# 3_audioConnectors.net
KiCad netlist of a schematic drawn in Altium Designer
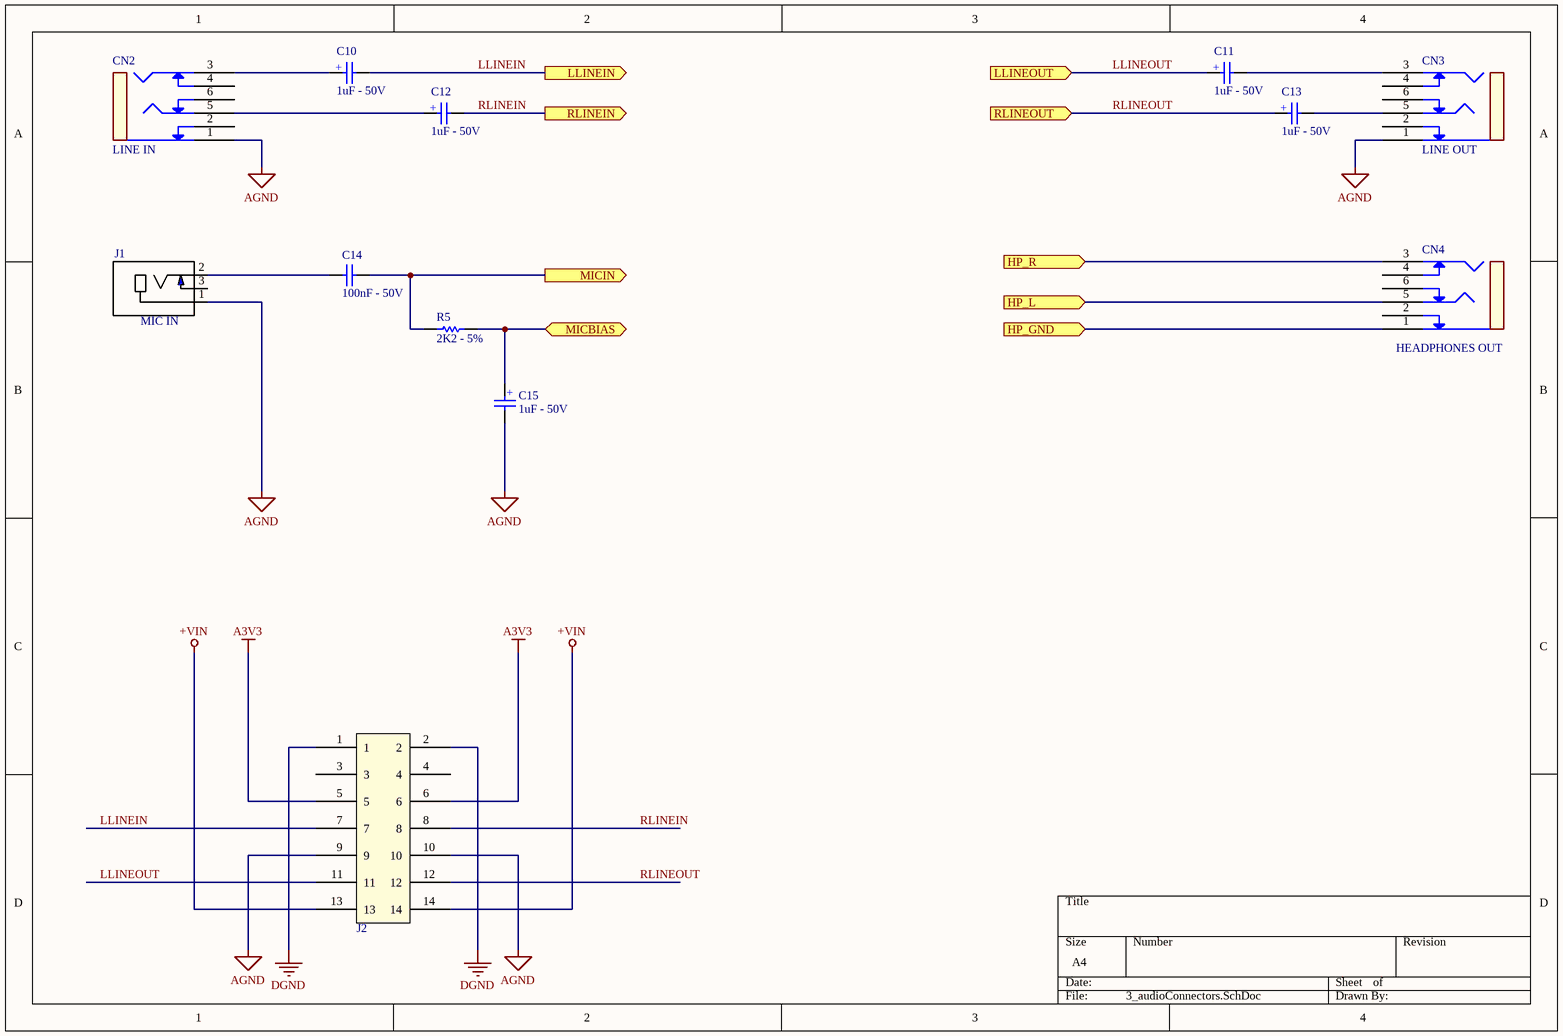
[diagram p0: 3_audioConnectors.SchDoc]

(export (version "E")
  (design (tool "Eeschema 10.0.6"))
  (components
    (comp (ref "C10")
      (value "Capacitor 1 uF - 10%")
      (footprint "CAP/SMD/ELET/5MM/NP")
      (description "Capacitor 1uF, 10%, SMD 0805")
      (fields
        (field (name "MANUFACTURER") "AVX")
        (field (name "PARTNUMBER") "08055C105KAT2A")
        (field (name "VALOR") "1uF - 50V")
      )
      (libsource (lib "Capacitor_smd") (part "1uF - 50V - 10% - 0805 - 3296"))
    )
    (comp (ref "C11")
      (value "Capacitor 1 uF - 10%")
      (footprint "CAP/SMD/ELET/5MM/NP")
      (description "Capacitor 1uF, 10%, SMD 0805")
      (fields
        (field (name "MANUFACTURER") "AVX")
        (field (name "PARTNUMBER") "08055C105KAT2A")
        (field (name "VALOR") "1uF - 50V")
      )
      (libsource (lib "Capacitor_smd") (part "1uF - 50V - 10% - 0805 - 3296"))
    )
    (comp (ref "C12")
      (value "Capacitor 1 uF - 10%")
      (footprint "CAP/SMD/ELET/5MM/NP")
      (description "Capacitor 1uF, 10%, SMD 0805")
      (fields
        (field (name "MANUFACTURER") "AVX")
        (field (name "PARTNUMBER") "08055C105KAT2A")
        (field (name "VALOR") "1uF - 50V")
      )
      (libsource (lib "Capacitor_smd") (part "1uF - 50V - 10% - 0805 - 3296"))
    )
    (comp (ref "C13")
      (value "Capacitor 1 uF - 10%")
      (footprint "CAP/SMD/ELET/5MM/NP")
      (description "Capacitor 1uF, 10%, SMD 0805")
      (fields
        (field (name "MANUFACTURER") "AVX")
        (field (name "PARTNUMBER") "08055C105KAT2A")
        (field (name "VALOR") "1uF - 50V")
      )
      (libsource (lib "Capacitor_smd") (part "1uF - 50V - 10% - 0805 - 3296"))
    )
    (comp (ref "C14")
      (value "Capacitor 100 nF - 10%")
      (footprint "SMD0805-CAP")
      (description "Capacitor 100nF, 10%, SMD 0805")
      (fields
        (field (name "MANUFACTURER") "AVX")
        (field (name "PARTNUMBER") "08055C104KAT2A")
        (field (name "VALOR") "100nF - 50V")
      )
      (libsource (lib "Capacitor_smd") (part "100nF - 50V - 10% - 0805 - 580"))
    )
    (comp (ref "C15")
      (value "Capacitor 1 uF - 10%")
      (footprint "CAP/SMD/ELET/5MM/NP")
      (description "Capacitor 1uF, 10%, SMD 0805")
      (fields
        (field (name "MANUFACTURER") "AVX")
        (field (name "PARTNUMBER") "08055C105KAT2A")
        (field (name "VALOR") "1uF - 50V")
      )
      (libsource (lib "Capacitor_smd") (part "1uF - 50V - 10% - 0805 - 3296"))
    )
    (comp (ref "CN2")
      (value "LINE IN")
      (footprint "CNC/P10/.080")
      (description "Conector JACK P10 ST P/ PC")
      (libsource (lib "") (part "CNC JACK P10 ST P/ PCI, HORIZ, TP - 749_1"))
    )
    (comp (ref "CN3")
      (value "LINE OUT")
      (footprint "CNC/P10/.080")
      (description "Conector JACK P10 ST P/ PC")
      (libsource (lib "Conector") (part "CNC JACK P10 ST P/ PCI, HORIZ, TP - 749"))
    )
    (comp (ref "CN4")
      (value "HEADPHONES OUT")
      (footprint "CNC/P10/.080")
      (description "Conector JACK P10 ST P/ PC")
      (libsource (lib "Conector") (part "CNC JACK P10 ST P/ PCI, HORIZ, TP - 749"))
    )
    (comp (ref "J1")
      (value "MIC IN")
      (footprint "CUI_MJ1-2510-SMT")
      (fields (field (name "Comment") "MJ1-2510-SMT"))
      (libsource (lib "MJ1-2510-SMT") (part "MJ1-2510-SMT"))
    )
    (comp (ref "J2")
      (value "BOARD SLOT CONNECTOR")
      (footprint "SLOT_CONN_BOARD")
      (description "Conector de expansão colocado na borda da placa")
      (libsource (lib "Não_padronizados") (part "SLOT_MACHO"))
    )
    (comp (ref "R5")
      (value "2K2 - 5% - 0805 - 333")
      (footprint "SMD0805")
      (description "Resistor 2K2, 5%, SMD 0805")
      (fields
        (field (name "PARTNUMBER") "RC2012J222CS")
        (field (name "MANUFACTURER") "SAMSUNG")
        (field (name "VALOR") "2K2 - 5%")
      )
      (libsource (lib "Resistor_smd") (part "2K2 - 5% - 0805 - 333"))
    )
  )
  (nets
    (net (code "1") (name "+VIN") (class "Default")
      (node (ref "J2") (pin "13") (pinfunction "13_13") (pintype "passive"))
      (node (ref "J2") (pin "14") (pinfunction "14_14") (pintype "passive"))
    )
    (net (code "2") (name "/HP_GND") (class "Default")
      (node (ref "CN4") (pin "1") (pinfunction "1_1") (pintype "passive"))
    )
    (net (code "3") (name "/HP_L") (class "Default")
      (node (ref "CN4") (pin "5") (pinfunction "5_5") (pintype "passive"))
    )
    (net (code "4") (name "/HP_R") (class "Default")
      (node (ref "CN4") (pin "3") (pinfunction "3_3") (pintype "passive"))
    )
    (net (code "5") (name "/LLINEIN") (class "Default")
      (node (ref "C10") (pin "1") (pinfunction "1_1") (pintype "passive"))
      (node (ref "J2") (pin "7") (pinfunction "7_7") (pintype "passive"))
    )
    (net (code "6") (name "/LLINEOUT") (class "Default")
      (node (ref "C11") (pin "2") (pinfunction "2_2") (pintype "passive"))
      (node (ref "J2") (pin "11") (pinfunction "11_11") (pintype "passive"))
    )
    (net (code "7") (name "/MICBIAS") (class "Default")
      (node (ref "C15") (pin "2") (pinfunction "2_2") (pintype "passive"))
      (node (ref "R5") (pin "2") (pinfunction "2_2") (pintype "passive"))
    )
    (net (code "8") (name "/MICIN") (class "Default")
      (node (ref "C14") (pin "2") (pinfunction "2_2") (pintype "passive"))
      (node (ref "R5") (pin "1") (pinfunction "1_1") (pintype "passive"))
    )
    (net (code "9") (name "/RLINEIN") (class "Default")
      (node (ref "C12") (pin "1") (pinfunction "1_1") (pintype "passive"))
      (node (ref "J2") (pin "8") (pinfunction "8_8") (pintype "passive"))
    )
    (net (code "10") (name "/RLINEOUT") (class "Default")
      (node (ref "C13") (pin "2") (pinfunction "2_2") (pintype "passive"))
      (node (ref "J2") (pin "12") (pinfunction "12_12") (pintype "passive"))
    )
    (net (code "11") (name "A3V3") (class "Default")
      (node (ref "J2") (pin "5") (pinfunction "5_5") (pintype "passive"))
      (node (ref "J2") (pin "6") (pinfunction "6_6") (pintype "passive"))
    )
    (net (code "12") (name "AGND") (class "Default")
      (node (ref "C15") (pin "1") (pinfunction "1_1") (pintype "passive"))
      (node (ref "CN2") (pin "1") (pinfunction "1_1") (pintype "passive"))
      (node (ref "CN3") (pin "1") (pinfunction "1_1") (pintype "passive"))
      (node (ref "J1") (pin "1") (pinfunction "1_1") (pintype "passive"))
      (node (ref "J2") (pin "10") (pinfunction "10_10") (pintype "passive"))
      (node (ref "J2") (pin "9") (pinfunction "9_9") (pintype "passive"))
    )
    (net (code "13") (name "DGND") (class "Default")
      (node (ref "J2") (pin "1") (pinfunction "1_1") (pintype "passive"))
      (node (ref "J2") (pin "2") (pinfunction "2_2") (pintype "passive"))
    )
    (net (code "14") (name "Net-(C10-Pad2)") (class "Default")
      (node (ref "C10") (pin "2") (pinfunction "2_2") (pintype "passive"))
      (node (ref "CN2") (pin "3") (pinfunction "3_3") (pintype "passive"))
    )
    (net (code "15") (name "Net-(C11-Pad1)") (class "Default")
      (node (ref "C11") (pin "1") (pinfunction "1_1") (pintype "passive"))
      (node (ref "CN3") (pin "3") (pinfunction "3_3") (pintype "passive"))
    )
    (net (code "16") (name "Net-(C12-Pad2)") (class "Default")
      (node (ref "C12") (pin "2") (pinfunction "2_2") (pintype "passive"))
      (node (ref "CN2") (pin "5") (pinfunction "5_5") (pintype "passive"))
    )
    (net (code "17") (name "Net-(C13-Pad1)") (class "Default")
      (node (ref "C13") (pin "1") (pinfunction "1_1") (pintype "passive"))
      (node (ref "CN3") (pin "5") (pinfunction "5_5") (pintype "passive"))
    )
    (net (code "18") (name "Net-(C14-Pad1)") (class "Default")
      (node (ref "C14") (pin "1") (pinfunction "1_1") (pintype "passive"))
      (node (ref "J1") (pin "2") (pinfunction "2_2") (pintype "passive"))
    )
    (net (code "19") (name "unconnected-(CN2-Pad2)") (class "Default")
      (node (ref "CN2") (pin "2") (pinfunction "2_2") (pintype "passive"))
    )
    (net (code "20") (name "unconnected-(CN2-Pad4)") (class "Default")
      (node (ref "CN2") (pin "4") (pinfunction "4_4") (pintype "passive"))
    )
    (net (code "21") (name "unconnected-(CN2-Pad6)") (class "Default")
      (node (ref "CN2") (pin "6") (pinfunction "6_6") (pintype "passive"))
    )
    (net (code "22") (name "unconnected-(CN3-Pad2)") (class "Default")
      (node (ref "CN3") (pin "2") (pinfunction "2_2") (pintype "passive"))
    )
    (net (code "23") (name "unconnected-(CN3-Pad4)") (class "Default")
      (node (ref "CN3") (pin "4") (pinfunction "4_4") (pintype "passive"))
    )
    (net (code "24") (name "unconnected-(CN3-Pad6)") (class "Default")
      (node (ref "CN3") (pin "6") (pinfunction "6_6") (pintype "passive"))
    )
    (net (code "25") (name "unconnected-(CN4-Pad2)") (class "Default")
      (node (ref "CN4") (pin "2") (pinfunction "2_2") (pintype "passive"))
    )
    (net (code "26") (name "unconnected-(CN4-Pad4)") (class "Default")
      (node (ref "CN4") (pin "4") (pinfunction "4_4") (pintype "passive"))
    )
    (net (code "27") (name "unconnected-(CN4-Pad6)") (class "Default")
      (node (ref "CN4") (pin "6") (pinfunction "6_6") (pintype "passive"))
    )
    (net (code "28") (name "unconnected-(J1-4-Pad3)") (class "Default")
      (node (ref "J1") (pin "3") (pinfunction "4_3") (pintype "passive"))
    )
    (net (code "29") (name "unconnected-(J2-Pad3)") (class "Default")
      (node (ref "J2") (pin "3") (pinfunction "3_3") (pintype "passive"))
    )
    (net (code "30") (name "unconnected-(J2-Pad4)") (class "Default")
      (node (ref "J2") (pin "4") (pinfunction "4_4") (pintype "passive"))
    )
  )
)
